# SH5_-_LCD_DISPLAY.net
KiCad netlist of a schematic drawn in Altium Designer
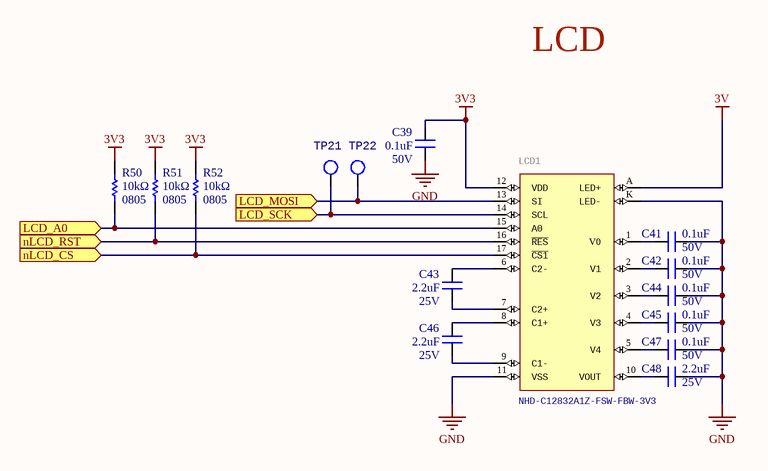
[diagram p0: SH5 - LCD DISPLAY.SchDoc]

(export (version "E")
  (design (tool "Eeschema 10.0.6"))
  (components
    (comp (ref "C39")
      (value "0.1uF")
      (footprint "CAPC2012X140N")
      (description "CAP CER 0.1UF 50V X7R 0805")
      (fields
        (field (name "TOLERANCE") "10%")
        (field (name "VOLTAGE RATING") "50V")
        (field (name "Comment") "CAP_0.1uF_50V_0805")
      )
      (libsource (lib "UWRT_Schematic_Library_2020") (part "CAP_0.1uF_50V_0805"))
    )
    (comp (ref "C41")
      (value "0.1uF")
      (footprint "CAPC2012X140N")
      (description "CAP CER 0.1UF 50V X7R 0805")
      (fields
        (field (name "TOLERANCE") "10%")
        (field (name "VOLTAGE RATING") "50V")
        (field (name "Comment") "CAP_0.1uF_50V_0805")
      )
      (libsource (lib "UWRT_Schematic_Library_2020") (part "CAP_0.1uF_50V_0805"))
    )
    (comp (ref "C42")
      (value "0.1uF")
      (footprint "CAPC2012X140N")
      (description "CAP CER 0.1UF 50V X7R 0805")
      (fields
        (field (name "TOLERANCE") "10%")
        (field (name "VOLTAGE RATING") "50V")
        (field (name "Comment") "CAP_0.1uF_50V_0805")
      )
      (libsource (lib "UWRT_Schematic_Library_2020") (part "CAP_0.1uF_50V_0805"))
    )
    (comp (ref "C43")
      (value "2.2uF")
      (footprint "CAPC2012X140N")
      (description "CAP CER 2.2UF 25V X7R 0805")
      (fields
        (field (name "TOLERANCE") "10%")
        (field (name "VOLTAGE RATING") "25V")
        (field (name "Comment") "CAP_2.2uF_25V_0805")
      )
      (libsource (lib "UWRT_Schematic_Library_2020") (part "CAP_2.2uF_25V_0805"))
    )
    (comp (ref "C44")
      (value "0.1uF")
      (footprint "CAPC2012X140N")
      (description "CAP CER 0.1UF 50V X7R 0805")
      (fields
        (field (name "TOLERANCE") "10%")
        (field (name "VOLTAGE RATING") "50V")
        (field (name "Comment") "CAP_0.1uF_50V_0805")
      )
      (libsource (lib "UWRT_Schematic_Library_2020") (part "CAP_0.1uF_50V_0805"))
    )
    (comp (ref "C45")
      (value "0.1uF")
      (footprint "CAPC2012X140N")
      (description "CAP CER 0.1UF 50V X7R 0805")
      (fields
        (field (name "TOLERANCE") "10%")
        (field (name "VOLTAGE RATING") "50V")
        (field (name "Comment") "CAP_0.1uF_50V_0805")
      )
      (libsource (lib "UWRT_Schematic_Library_2020") (part "CAP_0.1uF_50V_0805"))
    )
    (comp (ref "C46")
      (value "2.2uF")
      (footprint "CAPC2012X140N")
      (description "CAP CER 2.2UF 25V X7R 0805")
      (fields
        (field (name "TOLERANCE") "10%")
        (field (name "VOLTAGE RATING") "25V")
        (field (name "Comment") "CAP_2.2uF_25V_0805")
      )
      (libsource (lib "UWRT_Schematic_Library_2020") (part "CAP_2.2uF_25V_0805"))
    )
    (comp (ref "C47")
      (value "0.1uF")
      (footprint "CAPC2012X140N")
      (description "CAP CER 0.1UF 50V X7R 0805")
      (fields
        (field (name "TOLERANCE") "10%")
        (field (name "VOLTAGE RATING") "50V")
        (field (name "Comment") "CAP_0.1uF_50V_0805")
      )
      (libsource (lib "UWRT_Schematic_Library_2020") (part "CAP_0.1uF_50V_0805"))
    )
    (comp (ref "C48")
      (value "2.2uF")
      (footprint "CAPC2012X140N")
      (description "CAP CER 2.2UF 25V X7R 0805")
      (fields
        (field (name "TOLERANCE") "10%")
        (field (name "VOLTAGE RATING") "25V")
        (field (name "Comment") "CAP_2.2uF_25V_0805")
      )
      (libsource (lib "UWRT_Schematic_Library_2020") (part "CAP_2.2uF_25V_0805"))
    )
    (comp (ref "LCD1")
      (value "NHD-C12832A1Z-FSW-FBW-3V3")
      (footprint "NHDC12832A1ZFSWFBW3V3")
      (description "LCD COG GRAPHIC 128X32")
      (libsource (lib "UWRT_Schematic_Library_2020") (part "NHD-C12832A1Z-FSW-FBW-3V3"))
    )
    (comp (ref "R50")
      (value "10kΩ")
      (footprint "RESC2012X60N")
      (description "RES SMD 10K OHM 1% 1/8W 0805")
      (fields
        (field (name "CASE CODE (IMPERIAL)") "0805")
        (field (name "TOLERANCE") "1%")
        (field (name "Comment") "RES_10kΩ_0805")
      )
      (libsource (lib "UWRT_Schematic_Library_2020") (part "RES_10kΩ_0805"))
    )
    (comp (ref "R51")
      (value "10kΩ")
      (footprint "RESC2012X60N")
      (description "RES SMD 10K OHM 1% 1/8W 0805")
      (fields
        (field (name "CASE CODE (IMPERIAL)") "0805")
        (field (name "TOLERANCE") "1%")
        (field (name "Comment") "RES_10kΩ_0805")
      )
      (libsource (lib "UWRT_Schematic_Library_2020") (part "RES_10kΩ_0805"))
    )
    (comp (ref "R52")
      (value "10kΩ")
      (footprint "RESC2012X60N")
      (description "RES SMD 10K OHM 1% 1/8W 0805")
      (fields
        (field (name "CASE CODE (IMPERIAL)") "0805")
        (field (name "TOLERANCE") "1%")
        (field (name "Comment") "RES_10kΩ_0805")
      )
      (libsource (lib "UWRT_Schematic_Library_2020") (part "RES_10kΩ_0805"))
    )
    (comp (ref "TP21")
      (value "TESTPOINT_LOOP")
      (footprint "TESTPOINT_LOOP")
      (description "Loop testpoint through-hole pad")
      (libsource (lib "UWRT_Schematic_Library_2020") (part "TESTPOINT_LOOP"))
    )
    (comp (ref "TP22")
      (value "TESTPOINT_LOOP")
      (footprint "TESTPOINT_LOOP")
      (description "Loop testpoint through-hole pad")
      (libsource (lib "UWRT_Schematic_Library_2020") (part "TESTPOINT_LOOP"))
    )
  )
  (nets
    (net (code "1") (name "/LCD_A0") (class "Default")
      (node (ref "LCD1") (pin "15") (pinfunction "A0_15") (pintype "bidirectional"))
      (node (ref "R50") (pin "1") (pinfunction "1_1") (pintype "passive"))
    )
    (net (code "2") (name "/LCD_MOSI") (class "Default")
      (node (ref "LCD1") (pin "13") (pinfunction "SI_13") (pintype "bidirectional"))
      (node (ref "TP22") (pin "1") (pintype "passive"))
    )
    (net (code "3") (name "/LCD_SCK") (class "Default")
      (node (ref "LCD1") (pin "14") (pinfunction "SCL_14") (pintype "bidirectional"))
      (node (ref "TP21") (pin "1") (pintype "passive"))
    )
    (net (code "4") (name "/nLCD_CS") (class "Default")
      (node (ref "LCD1") (pin "17") (pinfunction "~{CS1}_17") (pintype "bidirectional"))
      (node (ref "R52") (pin "1") (pinfunction "1_1") (pintype "passive"))
    )
    (net (code "5") (name "/nLCD_RST") (class "Default")
      (node (ref "LCD1") (pin "16") (pinfunction "~{RES}_16") (pintype "bidirectional"))
      (node (ref "R51") (pin "1") (pinfunction "1_1") (pintype "passive"))
    )
    (net (code "6") (name "3V") (class "Default")
      (node (ref "LCD1") (pin "A") (pinfunction "LED+_A") (pintype "bidirectional"))
    )
    (net (code "7") (name "3V3") (class "Default")
      (node (ref "C39") (pin "1") (pinfunction "1_1") (pintype "passive"))
      (node (ref "LCD1") (pin "12") (pinfunction "VDD_12") (pintype "bidirectional"))
      (node (ref "R50") (pin "2") (pinfunction "2_2") (pintype "passive"))
      (node (ref "R51") (pin "2") (pinfunction "2_2") (pintype "passive"))
      (node (ref "R52") (pin "2") (pinfunction "2_2") (pintype "passive"))
    )
    (net (code "8") (name "GND") (class "Default")
      (node (ref "C39") (pin "2") (pinfunction "2_2") (pintype "passive"))
      (node (ref "C41") (pin "1") (pinfunction "1_1") (pintype "passive"))
      (node (ref "C42") (pin "1") (pinfunction "1_1") (pintype "passive"))
      (node (ref "C44") (pin "1") (pinfunction "1_1") (pintype "passive"))
      (node (ref "C45") (pin "1") (pinfunction "1_1") (pintype "passive"))
      (node (ref "C47") (pin "1") (pinfunction "1_1") (pintype "passive"))
      (node (ref "C48") (pin "1") (pinfunction "1_1") (pintype "passive"))
      (node (ref "LCD1") (pin "11") (pinfunction "VSS_11") (pintype "bidirectional"))
      (node (ref "LCD1") (pin "K") (pinfunction "LED-_K") (pintype "bidirectional"))
    )
    (net (code "9") (name "Net-(LCD1-C1+)") (class "Default")
      (node (ref "C46") (pin "2") (pinfunction "2_2") (pintype "passive"))
      (node (ref "LCD1") (pin "8") (pinfunction "C1+_8") (pintype "bidirectional"))
    )
    (net (code "10") (name "Net-(LCD1-C1-)") (class "Default")
      (node (ref "C46") (pin "1") (pinfunction "1_1") (pintype "passive"))
      (node (ref "LCD1") (pin "9") (pinfunction "C1-_9") (pintype "bidirectional"))
    )
    (net (code "11") (name "Net-(LCD1-C2+)") (class "Default")
      (node (ref "C43") (pin "1") (pinfunction "1_1") (pintype "passive"))
      (node (ref "LCD1") (pin "7") (pinfunction "C2+_7") (pintype "bidirectional"))
    )
    (net (code "12") (name "Net-(LCD1-C2-)") (class "Default")
      (node (ref "C43") (pin "2") (pinfunction "2_2") (pintype "passive"))
      (node (ref "LCD1") (pin "6") (pinfunction "C2-_6") (pintype "bidirectional"))
    )
    (net (code "13") (name "Net-(LCD1-V0)") (class "Default")
      (node (ref "C41") (pin "2") (pinfunction "2_2") (pintype "passive"))
      (node (ref "LCD1") (pin "1") (pinfunction "V0_1") (pintype "bidirectional"))
    )
    (net (code "14") (name "Net-(LCD1-V1)") (class "Default")
      (node (ref "C42") (pin "2") (pinfunction "2_2") (pintype "passive"))
      (node (ref "LCD1") (pin "2") (pinfunction "V1_2") (pintype "bidirectional"))
    )
    (net (code "15") (name "Net-(LCD1-V2)") (class "Default")
      (node (ref "C44") (pin "2") (pinfunction "2_2") (pintype "passive"))
      (node (ref "LCD1") (pin "3") (pinfunction "V2_3") (pintype "bidirectional"))
    )
    (net (code "16") (name "Net-(LCD1-V3)") (class "Default")
      (node (ref "C45") (pin "2") (pinfunction "2_2") (pintype "passive"))
      (node (ref "LCD1") (pin "4") (pinfunction "V3_4") (pintype "bidirectional"))
    )
    (net (code "17") (name "Net-(LCD1-V4)") (class "Default")
      (node (ref "C47") (pin "2") (pinfunction "2_2") (pintype "passive"))
      (node (ref "LCD1") (pin "5") (pinfunction "V4_5") (pintype "bidirectional"))
    )
    (net (code "18") (name "Net-(LCD1-VOUT)") (class "Default")
      (node (ref "C48") (pin "2") (pinfunction "2_2") (pintype "passive"))
      (node (ref "LCD1") (pin "10") (pinfunction "VOUT_10") (pintype "bidirectional"))
    )
  )
)
